# AutoReverse2.net
KiCad netlist of a schematic drawn in Altium Designer
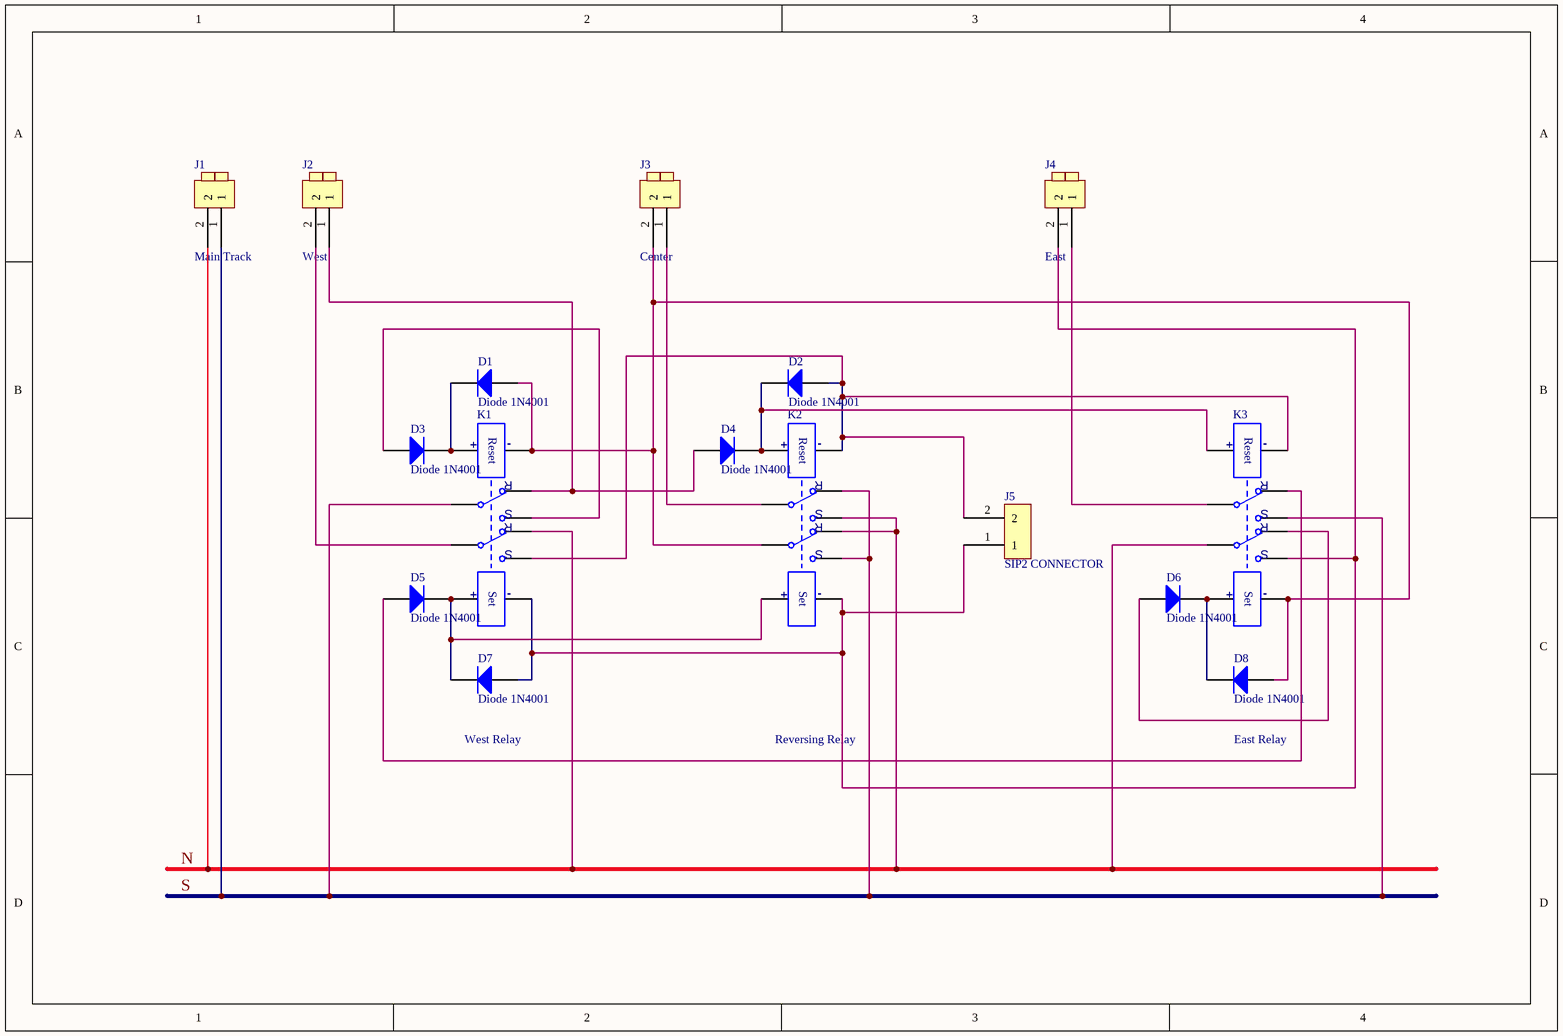
[diagram p0: AutoReverse2.SchDoc]

(export (version "E")
  (design (tool "Eeschema 10.0.6"))
  (components
    (comp (ref "D1")
      (value "Diode 1N4001")
      (footprint "AXIAL-0.3")
      (description "1 Amp General Purpose Rectifier")
      (fields (field (name "PUBLISHER") "Altium Limited"))
      (libsource (lib "Miscellaneous Devices") (part "Diode 1N4001"))
    )
    (comp (ref "D2")
      (value "Diode 1N4001")
      (footprint "AXIAL-0.3")
      (description "1 Amp General Purpose Rectifier")
      (fields (field (name "PUBLISHER") "Altium Limited"))
      (libsource (lib "Miscellaneous Devices") (part "Diode 1N4001"))
    )
    (comp (ref "D3")
      (value "Diode 1N4001")
      (footprint "AXIAL-0.3")
      (description "1 Amp General Purpose Rectifier")
      (fields (field (name "PUBLISHER") "Altium Limited"))
      (libsource (lib "Miscellaneous Devices") (part "Diode 1N4001"))
    )
    (comp (ref "D4")
      (value "Diode 1N4001")
      (footprint "AXIAL-0.3")
      (description "1 Amp General Purpose Rectifier")
      (fields (field (name "PUBLISHER") "Altium Limited"))
      (libsource (lib "Miscellaneous Devices") (part "Diode 1N4001"))
    )
    (comp (ref "D5")
      (value "Diode 1N4001")
      (footprint "AXIAL-0.3")
      (description "1 Amp General Purpose Rectifier")
      (fields (field (name "PUBLISHER") "Altium Limited"))
      (libsource (lib "Miscellaneous Devices") (part "Diode 1N4001"))
    )
    (comp (ref "D6")
      (value "Diode 1N4001")
      (footprint "AXIAL-0.3")
      (description "1 Amp General Purpose Rectifier")
      (fields (field (name "PUBLISHER") "Altium Limited"))
      (libsource (lib "Miscellaneous Devices") (part "Diode 1N4001"))
    )
    (comp (ref "D7")
      (value "Diode 1N4001")
      (footprint "AXIAL-0.3")
      (description "1 Amp General Purpose Rectifier")
      (fields (field (name "PUBLISHER") "Altium Limited"))
      (libsource (lib "Miscellaneous Devices") (part "Diode 1N4001"))
    )
    (comp (ref "D8")
      (value "Diode 1N4001")
      (footprint "AXIAL-0.3")
      (description "1 Amp General Purpose Rectifier")
      (fields (field (name "PUBLISHER") "Altium Limited"))
      (libsource (lib "Miscellaneous Devices") (part "Diode 1N4001"))
    )
    (comp (ref "J1")
      (value "Main Track")
      (footprint "Screw Terminal 2 way 0.2")
      (libsource (lib "Custom") (part "Screw Terminal 2 Way"))
    )
    (comp (ref "J2")
      (value "West")
      (footprint "Screw Terminal 2 way 0.2")
      (libsource (lib "Custom") (part "Screw Terminal 2 Way"))
    )
    (comp (ref "J3")
      (value "Center")
      (footprint "Screw Terminal 2 way 0.2")
      (libsource (lib "Custom") (part "Screw Terminal 2 Way"))
    )
    (comp (ref "J4")
      (value "East")
      (footprint "Screw Terminal 2 way 0.2")
      (libsource (lib "Custom") (part "Screw Terminal 2 Way"))
    )
    (comp (ref "J5")
      (value "SIP2 CONNECTOR")
      (footprint "HDR1X2")
      (libsource (lib "Custom") (part "SIP2 CONNECTOR"))
    )
    (comp (ref "K1")
      (value "West Relay")
      (footprint "DIP-10")
      (description "EA2-5T Dual Coil 5V Latching Relay")
      (fields (field (name "PUBLISHER") "Altium Limited"))
      (libsource (lib "Custom") (part "EA2-5T Dual Coil 5V Latching Relay"))
    )
    (comp (ref "K2")
      (value "Reversing Relay")
      (footprint "DIP-10")
      (description "EA2-5T Dual Coil 5V Latching Relay")
      (fields (field (name "PUBLISHER") "Altium Limited"))
      (libsource (lib "Custom") (part "EA2-5T Dual Coil 5V Latching Relay"))
    )
    (comp (ref "K3")
      (value "East Relay")
      (footprint "DIP-10")
      (description "EA2-5T Dual Coil 5V Latching Relay")
      (fields (field (name "PUBLISHER") "Altium Limited"))
      (libsource (lib "Custom") (part "EA2-5T Dual Coil 5V Latching Relay"))
    )
  )
  (nets
    (net (code "1") (name "/N") (class "Default")
      (node (ref "J1") (pin "2") (pinfunction "2_2") (pintype "passive"))
      (node (ref "K1") (pin "9") (pinfunction "R_9") (pintype "passive"))
      (node (ref "K2") (pin "4") (pinfunction "S_4") (pintype "passive"))
      (node (ref "K2") (pin "9") (pinfunction "R_9") (pintype "passive"))
      (node (ref "K3") (pin "8") (pinfunction "8_8") (pintype "passive"))
    )
    (net (code "2") (name "/S") (class "Default")
      (node (ref "J1") (pin "1") (pinfunction "1_1") (pintype "passive"))
      (node (ref "K1") (pin "3") (pinfunction "3_3") (pintype "passive"))
      (node (ref "K2") (pin "2") (pinfunction "R_2") (pintype "passive"))
      (node (ref "K2") (pin "7") (pinfunction "S_7") (pintype "passive"))
      (node (ref "K3") (pin "4") (pinfunction "S_4") (pintype "passive"))
    )
    (net (code "3") (name "Net-(D1-A)") (class "Default")
      (node (ref "D1") (pin "1") (pinfunction "A_1") (pintype "passive"))
      (node (ref "D8") (pin "1") (pinfunction "A_1") (pintype "passive"))
      (node (ref "J3") (pin "2") (pinfunction "2_2") (pintype "passive"))
      (node (ref "K1") (pin "6") (pintype "passive"))
      (node (ref "K2") (pin "8") (pinfunction "8_8") (pintype "passive"))
      (node (ref "K3") (pin "5") (pintype "passive"))
    )
    (net (code "4") (name "Net-(D1-K)") (class "Default")
      (node (ref "D1") (pin "2") (pinfunction "K_2") (pintype "passive"))
      (node (ref "D3") (pin "2") (pinfunction "K_2") (pintype "passive"))
      (node (ref "K1") (pin "10") (pintype "passive"))
    )
    (net (code "5") (name "Net-(D2-A)") (class "Default")
      (node (ref "D2") (pin "1") (pinfunction "A_1") (pintype "passive"))
      (node (ref "J5") (pin "2") (pinfunction "2_2") (pintype "passive"))
      (node (ref "K1") (pin "7") (pinfunction "S_7") (pintype "passive"))
      (node (ref "K2") (pin "6") (pintype "passive"))
      (node (ref "K3") (pin "6") (pintype "passive"))
    )
    (net (code "6") (name "Net-(D2-K)") (class "Default")
      (node (ref "D2") (pin "2") (pinfunction "K_2") (pintype "passive"))
      (node (ref "D4") (pin "2") (pinfunction "K_2") (pintype "passive"))
      (node (ref "K2") (pin "10") (pintype "passive"))
      (node (ref "K3") (pin "10") (pintype "passive"))
    )
    (net (code "7") (name "Net-(D3-A)") (class "Default")
      (node (ref "D3") (pin "1") (pinfunction "A_1") (pintype "passive"))
      (node (ref "K1") (pin "4") (pinfunction "S_4") (pintype "passive"))
    )
    (net (code "8") (name "Net-(D4-A)") (class "Default")
      (node (ref "D4") (pin "1") (pinfunction "A_1") (pintype "passive"))
      (node (ref "J2") (pin "1") (pinfunction "1_1") (pintype "passive"))
      (node (ref "K1") (pin "2") (pinfunction "R_2") (pintype "passive"))
    )
    (net (code "9") (name "Net-(D5-A)") (class "Default")
      (node (ref "D5") (pin "1") (pinfunction "A_1") (pintype "passive"))
      (node (ref "K3") (pin "2") (pinfunction "R_2") (pintype "passive"))
    )
    (net (code "10") (name "Net-(D5-K)") (class "Default")
      (node (ref "D5") (pin "2") (pinfunction "K_2") (pintype "passive"))
      (node (ref "D7") (pin "2") (pinfunction "K_2") (pintype "passive"))
      (node (ref "K1") (pin "1") (pintype "passive"))
      (node (ref "K2") (pin "1") (pintype "passive"))
    )
    (net (code "11") (name "Net-(D6-A)") (class "Default")
      (node (ref "D6") (pin "1") (pinfunction "A_1") (pintype "passive"))
      (node (ref "K3") (pin "9") (pinfunction "R_9") (pintype "passive"))
    )
    (net (code "12") (name "Net-(D6-K)") (class "Default")
      (node (ref "D6") (pin "2") (pinfunction "K_2") (pintype "passive"))
      (node (ref "D8") (pin "2") (pinfunction "K_2") (pintype "passive"))
      (node (ref "K3") (pin "1") (pintype "passive"))
    )
    (net (code "13") (name "Net-(D7-A)") (class "Default")
      (node (ref "D7") (pin "1") (pinfunction "A_1") (pintype "passive"))
      (node (ref "J4") (pin "2") (pinfunction "2_2") (pintype "passive"))
      (node (ref "J5") (pin "1") (pinfunction "1_1") (pintype "passive"))
      (node (ref "K1") (pin "5") (pintype "passive"))
      (node (ref "K2") (pin "5") (pintype "passive"))
      (node (ref "K3") (pin "7") (pinfunction "S_7") (pintype "passive"))
    )
    (net (code "14") (name "Net-(J2-Pad2)") (class "Default")
      (node (ref "J2") (pin "2") (pinfunction "2_2") (pintype "passive"))
      (node (ref "K1") (pin "8") (pinfunction "8_8") (pintype "passive"))
    )
    (net (code "15") (name "Net-(J3-Pad1)") (class "Default")
      (node (ref "J3") (pin "1") (pinfunction "1_1") (pintype "passive"))
      (node (ref "K2") (pin "3") (pinfunction "3_3") (pintype "passive"))
    )
    (net (code "16") (name "Net-(J4-Pad1)") (class "Default")
      (node (ref "J4") (pin "1") (pinfunction "1_1") (pintype "passive"))
      (node (ref "K3") (pin "3") (pinfunction "3_3") (pintype "passive"))
    )
  )
)
